# untitled.net
KiCad netlist of a schematic drawn in EAGLE
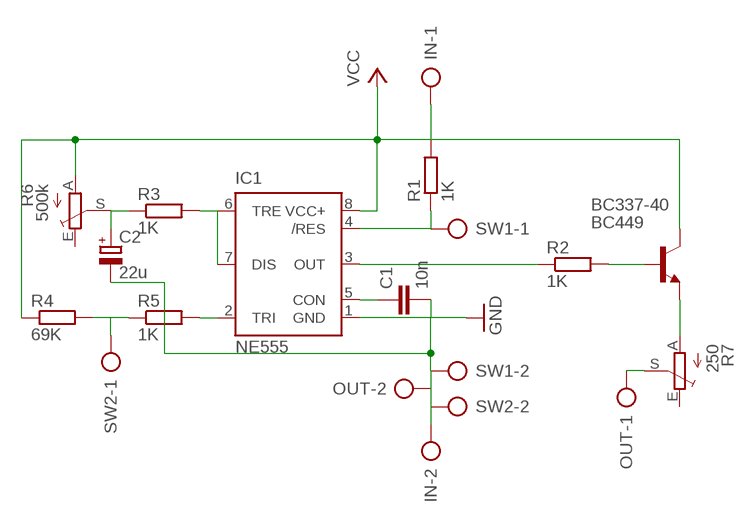
[diagram p0: schematic, sheet 1]

(export (version "E")
  (design (tool "Eeschema 10.0.6"))
  (components
    (comp (ref "BC337-40")
      (value "BC449")
      (footprint "eagle-import:TO92-EBC")
      (libsource (lib "eagle-import") (part "BC449"))
    )
    (comp (ref "C1")
      (value "10n")
      (footprint "eagle-import:C050-024X044")
      (libsource (lib "eagle-import") (part "C-EU050-024X044"))
    )
    (comp (ref "C2")
      (value "22u")
      (footprint "eagle-import:E2,5-5")
      (libsource (lib "eagle-import") (part "CPOL-EUE2.5-5"))
    )
    (comp (ref "IC1")
      (value "NE555")
      (footprint "eagle-import:DIL-08")
      (fields (field (name "MF") "Arrow Electronics") (field (name "MPN") "NE555N"))
      (libsource (lib "eagle-import") (part "NE555"))
    )
    (comp (ref "IN")
      (value "AK500/2")
      (footprint "eagle-import:AK500_2")
      (libsource (lib "eagle-import") (part "AK500/2"))
    )
    (comp (ref "OUT")
      (value "AK500/2")
      (footprint "eagle-import:AK500_2")
      (libsource (lib "eagle-import") (part "AK500/2"))
    )
    (comp (ref "R1")
      (value "1K")
      (footprint "eagle-import:0204_7")
      (libsource (lib "eagle-import") (part "R-EU_0204/7"))
    )
    (comp (ref "R2")
      (value "1K")
      (footprint "eagle-import:0204_7")
      (libsource (lib "eagle-import") (part "R-EU_0204/7"))
    )
    (comp (ref "R3")
      (value "1K")
      (footprint "eagle-import:0204_7")
      (libsource (lib "eagle-import") (part "R-EU_0204/7"))
    )
    (comp (ref "R4")
      (value "69K")
      (footprint "eagle-import:0204_7")
      (libsource (lib "eagle-import") (part "R-EU_0204/7"))
    )
    (comp (ref "R5")
      (value "1K")
      (footprint "eagle-import:0204_7")
      (libsource (lib "eagle-import") (part "R-EU_0204/7"))
    )
    (comp (ref "R6")
      (value "500k")
      (footprint "eagle-import:CA6V")
      (libsource (lib "eagle-import") (part "TRIM_EU-CA6V"))
    )
    (comp (ref "R7")
      (value "250")
      (footprint "eagle-import:CA6V")
      (libsource (lib "eagle-import") (part "TRIM_EU-CA6V"))
    )
    (comp (ref "SW1")
      (value "AK500/2")
      (footprint "eagle-import:AK500_2")
      (libsource (lib "eagle-import") (part "AK500/2"))
    )
    (comp (ref "SW2")
      (value "AK500/2")
      (footprint "eagle-import:AK500_2")
      (libsource (lib "eagle-import") (part "AK500/2"))
    )
  )
  (nets
    (net (code "1") (name "GND") (class "Default")
      (node (ref "C1") (pin "2") (pinfunction "2_2") (pintype "passive"))
      (node (ref "C2") (pin "-") (pinfunction "-_-") (pintype "passive"))
      (node (ref "IC1") (pin "1") (pinfunction "GND_1") (pintype "power_in"))
      (node (ref "IN") (pin "2") (pinfunction "KL_2") (pintype "passive"))
      (node (ref "OUT") (pin "2") (pinfunction "KL_2") (pintype "passive"))
      (node (ref "SW1") (pin "2") (pinfunction "KL_2") (pintype "passive"))
      (node (ref "SW2") (pin "2") (pinfunction "KL_2") (pintype "passive"))
    )
    (net (code "2") (name "Net-(BC337-40-PadB)") (class "Default")
      (node (ref "BC337-40") (pin "B") (pinfunction "B_B") (pintype "passive"))
      (node (ref "R2") (pin "2") (pinfunction "2_2") (pintype "passive"))
    )
    (net (code "3") (name "Net-(BC337-40-PadE)") (class "Default")
      (node (ref "BC337-40") (pin "E") (pinfunction "E_E") (pintype "passive"))
      (node (ref "R7") (pin "A") (pinfunction "A_A") (pintype "passive"))
    )
    (net (code "4") (name "Net-(C2-Pad+)") (class "Default")
      (node (ref "C2") (pin "+") (pinfunction "+_+") (pintype "passive"))
      (node (ref "R3") (pin "1") (pinfunction "1_1") (pintype "passive"))
      (node (ref "R6") (pin "S") (pinfunction "S_S") (pintype "passive"))
    )
    (net (code "5") (name "Net-(IC1-CON)") (class "Default")
      (node (ref "C1") (pin "1") (pinfunction "1_1") (pintype "passive"))
      (node (ref "IC1") (pin "5") (pinfunction "CON_5") (pintype "input"))
    )
    (net (code "6") (name "Net-(IC1-DIS)") (class "Default")
      (node (ref "IC1") (pin "6") (pinfunction "TRE_6") (pintype "input"))
      (node (ref "IC1") (pin "7") (pinfunction "DIS_7") (pintype "input"))
      (node (ref "R3") (pin "2") (pinfunction "2_2") (pintype "passive"))
    )
    (net (code "7") (name "Net-(IC1-OUT)") (class "Default")
      (node (ref "IC1") (pin "3") (pinfunction "OUT_3") (pintype "output"))
      (node (ref "R2") (pin "1") (pinfunction "1_1") (pintype "passive"))
    )
    (net (code "8") (name "Net-(IC1-TRI)") (class "Default")
      (node (ref "IC1") (pin "2") (pinfunction "TRI_2") (pintype "input"))
      (node (ref "R5") (pin "2") (pinfunction "2_2") (pintype "passive"))
    )
    (net (code "9") (name "Net-(IC1-{slash}RES)") (class "Default")
      (node (ref "IC1") (pin "4") (pinfunction "/RES_4") (pintype "input"))
      (node (ref "R1") (pin "1") (pinfunction "1_1") (pintype "passive"))
      (node (ref "SW1") (pin "1") (pinfunction "KL_1") (pintype "passive"))
    )
    (net (code "10") (name "Net-(OUTA-KL)") (class "Default")
      (node (ref "OUT") (pin "1") (pinfunction "KL_1") (pintype "passive"))
      (node (ref "R7") (pin "S") (pinfunction "S_S") (pintype "passive"))
    )
    (net (code "11") (name "Net-(SW2A-KL)") (class "Default")
      (node (ref "R4") (pin "2") (pinfunction "2_2") (pintype "passive"))
      (node (ref "R5") (pin "1") (pinfunction "1_1") (pintype "passive"))
      (node (ref "SW2") (pin "1") (pinfunction "KL_1") (pintype "passive"))
    )
    (net (code "12") (name "VCC") (class "Default")
      (node (ref "BC337-40") (pin "C") (pinfunction "C_C") (pintype "passive"))
      (node (ref "IC1") (pin "8") (pinfunction "VCC+_8") (pintype "power_in"))
      (node (ref "IN") (pin "1") (pinfunction "KL_1") (pintype "passive"))
      (node (ref "R1") (pin "2") (pinfunction "2_2") (pintype "passive"))
      (node (ref "R4") (pin "1") (pinfunction "1_1") (pintype "passive"))
      (node (ref "R6") (pin "A") (pinfunction "A_A") (pintype "passive"))
    )
    (net (code "13") (name "unconnected-(R6-PadE)") (class "Default")
      (node (ref "R6") (pin "E") (pinfunction "E_E") (pintype "passive"))
    )
    (net (code "14") (name "unconnected-(R7-PadE)") (class "Default")
      (node (ref "R7") (pin "E") (pinfunction "E_E") (pintype "passive"))
    )
  )
)
